# LEDLights.net
KiCad netlist of a schematic drawn in Altium Designer
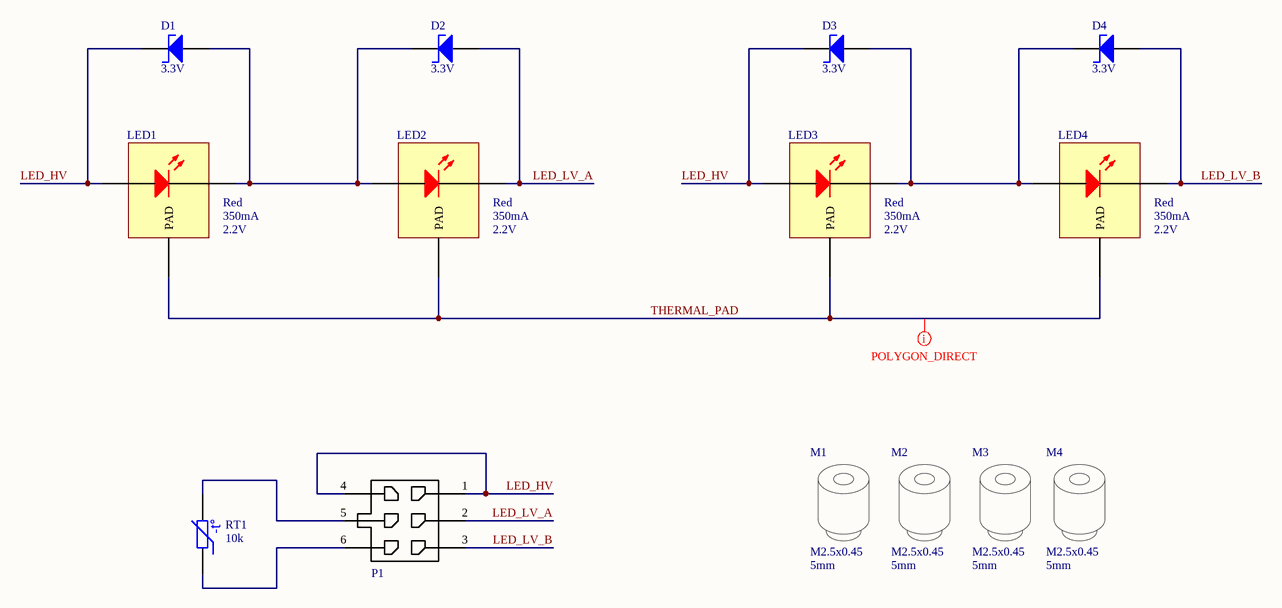
[diagram p0: LEDLights.SchDoc]

(export (version "E")
  (design (tool "Eeschema 10.0.6"))
  (components
    (comp (ref "D1")
      (value "DIODE ZENER 3.3V 3W DO-214AA")
      (footprint "DO-214AA Diode")
      (description "Diode Zener Single 3.3V 5% 3000mW Automotive 2-Pin SMB T/R")
      (fields
        (field (name "MANUFACTURER") "ON Semiconductor")
        (field (name "MANUFACTURER PART NUMBER") "SZ1SMB5913BT3G")
        (field (name "ZENER VOLTAGE") "3.3V")
      )
      (libsource (lib "Schematic Diagrams") (part "DIODE ZENER 3.3V 3W DO-214AA"))
    )
    (comp (ref "D2")
      (value "DIODE ZENER 3.3V 3W DO-214AA")
      (footprint "DO-214AA Diode")
      (description "Diode Zener Single 3.3V 5% 3000mW Automotive 2-Pin SMB T/R")
      (fields
        (field (name "MANUFACTURER") "ON Semiconductor")
        (field (name "MANUFACTURER PART NUMBER") "SZ1SMB5913BT3G")
        (field (name "ZENER VOLTAGE") "3.3V")
      )
      (libsource (lib "Schematic Diagrams") (part "DIODE ZENER 3.3V 3W DO-214AA"))
    )
    (comp (ref "D3")
      (value "DIODE ZENER 3.3V 3W DO-214AA")
      (footprint "DO-214AA Diode")
      (description "Diode Zener Single 3.3V 5% 3000mW Automotive 2-Pin SMB T/R")
      (fields
        (field (name "MANUFACTURER") "ON Semiconductor")
        (field (name "MANUFACTURER PART NUMBER") "SZ1SMB5913BT3G")
        (field (name "ZENER VOLTAGE") "3.3V")
      )
      (libsource (lib "Schematic Diagrams") (part "DIODE ZENER 3.3V 3W DO-214AA"))
    )
    (comp (ref "D4")
      (value "DIODE ZENER 3.3V 3W DO-214AA")
      (footprint "DO-214AA Diode")
      (description "Diode Zener Single 3.3V 5% 3000mW Automotive 2-Pin SMB T/R")
      (fields
        (field (name "MANUFACTURER") "ON Semiconductor")
        (field (name "MANUFACTURER PART NUMBER") "SZ1SMB5913BT3G")
        (field (name "ZENER VOLTAGE") "3.3V")
      )
      (libsource (lib "Schematic Diagrams") (part "DIODE ZENER 3.3V 3W DO-214AA"))
    )
    (comp (ref "LED1")
      (value "LED RED XLAMP XP-E2 1414")
      (footprint "LED XLAMP XP-E2 1414")
      (description "LED Lighting Color XLamp® XP-E2 Red 623nm (620nm ~ 625nm) 1414 (3535 Metric)")
      (fields
        (field (name "MANUFACTURER") "Cree")
        (field (name "MANUFACTURER PART NUMBER") "XPEBRD-L1-0000-00902")
        (field (name "COLOR") "Red")
        (field (name "TEST CURRENT") "350mA")
        (field (name "FORWARD VOLTAGE") "2.2V")
      )
      (libsource (lib "Schematic Diagrams") (part "LED RED XLAMP XP-E2 1414"))
    )
    (comp (ref "LED2")
      (value "LED RED XLAMP XP-E2 1414")
      (footprint "LED XLAMP XP-E2 1414")
      (description "LED Lighting Color XLamp® XP-E2 Red 623nm (620nm ~ 625nm) 1414 (3535 Metric)")
      (fields
        (field (name "MANUFACTURER") "Cree")
        (field (name "MANUFACTURER PART NUMBER") "XPEBRD-L1-0000-00902")
        (field (name "COLOR") "Red")
        (field (name "TEST CURRENT") "350mA")
        (field (name "FORWARD VOLTAGE") "2.2V")
      )
      (libsource (lib "Schematic Diagrams") (part "LED RED XLAMP XP-E2 1414"))
    )
    (comp (ref "LED3")
      (value "LED RED XLAMP XP-E2 1414")
      (footprint "LED XLAMP XP-E2 1414")
      (description "LED Lighting Color XLamp® XP-E2 Red 623nm (620nm ~ 625nm) 1414 (3535 Metric)")
      (fields
        (field (name "MANUFACTURER") "Cree")
        (field (name "MANUFACTURER PART NUMBER") "XPEBRD-L1-0000-00902")
        (field (name "COLOR") "Red")
        (field (name "TEST CURRENT") "350mA")
        (field (name "FORWARD VOLTAGE") "2.2V")
      )
      (libsource (lib "Schematic Diagrams") (part "LED RED XLAMP XP-E2 1414"))
    )
    (comp (ref "LED4")
      (value "LED RED XLAMP XP-E2 1414")
      (footprint "LED XLAMP XP-E2 1414")
      (description "LED Lighting Color XLamp® XP-E2 Red 623nm (620nm ~ 625nm) 1414 (3535 Metric)")
      (fields
        (field (name "MANUFACTURER") "Cree")
        (field (name "MANUFACTURER PART NUMBER") "XPEBRD-L1-0000-00902")
        (field (name "COLOR") "Red")
        (field (name "TEST CURRENT") "350mA")
        (field (name "FORWARD VOLTAGE") "2.2V")
      )
      (libsource (lib "Schematic Diagrams") (part "LED RED XLAMP XP-E2 1414"))
    )
    (comp (ref "M1")
      (value "STANDOFF RND M2.5X0.45 STEEL 5MM")
      (footprint "M2.5 Standoff")
      (fields
        (field (name "MANUFACTURER") "Wurth Electronics")
        (field (name "MANUFACTURER PART NUMBER") "9774050151R")
        (field (name "SCREW-THREAD SIZE") "M2.5x0.45")
        (field (name "STANDOFF HEIGHT") "5mm")
      )
      (libsource (lib "Schematic Diagrams") (part "STANDOFF RND M2.5X0.45 STEEL 5MM"))
    )
    (comp (ref "M2")
      (value "STANDOFF RND M2.5X0.45 STEEL 5MM")
      (footprint "M2.5 Standoff")
      (fields
        (field (name "MANUFACTURER") "Wurth Electronics")
        (field (name "MANUFACTURER PART NUMBER") "9774050151R")
        (field (name "SCREW-THREAD SIZE") "M2.5x0.45")
        (field (name "STANDOFF HEIGHT") "5mm")
      )
      (libsource (lib "Schematic Diagrams") (part "STANDOFF RND M2.5X0.45 STEEL 5MM"))
    )
    (comp (ref "M3")
      (value "STANDOFF RND M2.5X0.45 STEEL 5MM")
      (footprint "M2.5 Standoff")
      (fields
        (field (name "MANUFACTURER") "Wurth Electronics")
        (field (name "MANUFACTURER PART NUMBER") "9774050151R")
        (field (name "SCREW-THREAD SIZE") "M2.5x0.45")
        (field (name "STANDOFF HEIGHT") "5mm")
      )
      (libsource (lib "Schematic Diagrams") (part "STANDOFF RND M2.5X0.45 STEEL 5MM"))
    )
    (comp (ref "M4")
      (value "STANDOFF RND M2.5X0.45 STEEL 5MM")
      (footprint "M2.5 Standoff")
      (fields
        (field (name "MANUFACTURER") "Wurth Electronics")
        (field (name "MANUFACTURER PART NUMBER") "9774050151R")
        (field (name "SCREW-THREAD SIZE") "M2.5x0.45")
        (field (name "STANDOFF HEIGHT") "5mm")
      )
      (libsource (lib "Schematic Diagrams") (part "STANDOFF RND M2.5X0.45 STEEL 5MM"))
    )
    (comp (ref "P1")
      (value "CONN 6POS MICRO-FIT 2ROW 3mm")
      (footprint "CONN, 6POS MICRO-FIT")
      (description "Header; 2 Row; Vertical; Polarizing Peg; 6 Pin; Tin Plate; SMT/Glow Wire; Kinked Leads")
      (fields (field (name "MANUFACTURER") "Molex") (field (name "MANUFACTURER PART NUMBER") "0430450612"))
      (libsource (lib "Schematic Diagrams") (part "CONN 6POS MICRO-FIT 2ROW 3mm"))
    )
    (comp (ref "RT1")
      (value "NTC THERMISTORS 10K 0603 SMD")
      (footprint "RES, 0603")
      (description "NTC THERMISTORS 10KOHM 1608 SMD")
      (fields
        (field (name "MANUFACTURER") "Murata Electronics North America")
        (field (name "MANUFACTURER PART NUMBER") "NCU18XH103F60RB")
        (field (name "RESISTANCE IN OHMS @ 25°C") "10k")
      )
      (libsource (lib "Schematic Diagrams") (part "NTC THERMISTORS 10K 0603 SMD"))
    )
  )
  (nets
    (net (code "1") (name "/LED_HV") (class "Default")
      (node (ref "D1") (pin "2") (pinfunction "K_2") (pintype "passive"))
      (node (ref "D3") (pin "2") (pinfunction "K_2") (pintype "passive"))
      (node (ref "LED1") (pin "1") (pinfunction "A_1") (pintype "passive"))
      (node (ref "LED3") (pin "1") (pinfunction "A_1") (pintype "passive"))
      (node (ref "P1") (pin "1") (pinfunction "1_1") (pintype "passive"))
      (node (ref "P1") (pin "4") (pinfunction "4_4") (pintype "passive"))
    )
    (net (code "2") (name "/LED_LV_A") (class "Default")
      (node (ref "D2") (pin "1") (pinfunction "A_1") (pintype "passive"))
      (node (ref "LED2") (pin "3") (pinfunction "K_3") (pintype "passive"))
      (node (ref "P1") (pin "2") (pinfunction "2_2") (pintype "passive"))
    )
    (net (code "3") (name "/LED_LV_B") (class "Default")
      (node (ref "D4") (pin "1") (pinfunction "A_1") (pintype "passive"))
      (node (ref "LED4") (pin "3") (pinfunction "K_3") (pintype "passive"))
      (node (ref "P1") (pin "3") (pinfunction "3_3") (pintype "passive"))
    )
    (net (code "4") (name "/THERMAL_PAD") (class "Default")
      (node (ref "LED1") (pin "2") (pinfunction "PAD_2") (pintype "passive"))
      (node (ref "LED2") (pin "2") (pinfunction "PAD_2") (pintype "passive"))
      (node (ref "LED3") (pin "2") (pinfunction "PAD_2") (pintype "passive"))
      (node (ref "LED4") (pin "2") (pinfunction "PAD_2") (pintype "passive"))
    )
    (net (code "5") (name "Net-(D1-A)") (class "Default")
      (node (ref "D1") (pin "1") (pinfunction "A_1") (pintype "passive"))
      (node (ref "D2") (pin "2") (pinfunction "K_2") (pintype "passive"))
      (node (ref "LED1") (pin "3") (pinfunction "K_3") (pintype "passive"))
      (node (ref "LED2") (pin "1") (pinfunction "A_1") (pintype "passive"))
    )
    (net (code "6") (name "Net-(D3-A)") (class "Default")
      (node (ref "D3") (pin "1") (pinfunction "A_1") (pintype "passive"))
      (node (ref "D4") (pin "2") (pinfunction "K_2") (pintype "passive"))
      (node (ref "LED3") (pin "3") (pinfunction "K_3") (pintype "passive"))
      (node (ref "LED4") (pin "1") (pinfunction "A_1") (pintype "passive"))
    )
    (net (code "7") (name "Net-(P1-Pad5)") (class "Default")
      (node (ref "P1") (pin "5") (pinfunction "5_5") (pintype "passive"))
      (node (ref "RT1") (pin "2") (pinfunction "2_2") (pintype "passive"))
    )
    (net (code "8") (name "Net-(P1-Pad6)") (class "Default")
      (node (ref "P1") (pin "6") (pinfunction "6_6") (pintype "passive"))
      (node (ref "RT1") (pin "1") (pinfunction "1_1") (pintype "passive"))
    )
  )
)
